# robot.net
KiCad netlist of a schematic drawn in EAGLE
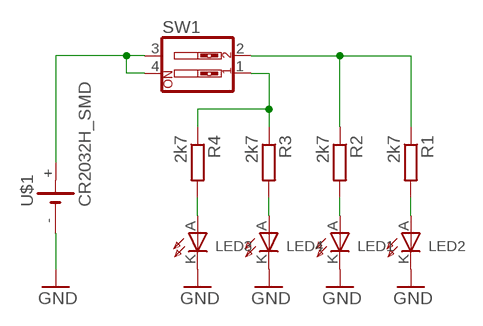
[diagram p0: schematic, sheet 1]

(export (version "E")
  (design (tool "Eeschema 10.0.6"))
  (components
    (comp (ref "LED1")
      (value "LEDREAR")
      (footprint "eagle-import:3MM_REAR")
      (libsource (lib "eagle-import") (part "LEDREAR"))
    )
    (comp (ref "LED2")
      (value "LEDREAR")
      (footprint "eagle-import:3MM_REAR")
      (libsource (lib "eagle-import") (part "LEDREAR"))
    )
    (comp (ref "LED3")
      (value "LED3MMH")
      (footprint "eagle-import:3MM_H")
      (libsource (lib "eagle-import") (part "LED3MMH"))
    )
    (comp (ref "LED4")
      (value "LED3MMH")
      (footprint "eagle-import:3MM_H")
      (libsource (lib "eagle-import") (part "LED3MMH"))
    )
    (comp (ref "R1")
      (value "2k7")
      (footprint "eagle-import:0204_7")
      (libsource (lib "eagle-import") (part "R-EU_0204/7"))
    )
    (comp (ref "R2")
      (value "2k7")
      (footprint "eagle-import:0204_7")
      (libsource (lib "eagle-import") (part "R-EU_0204/7"))
    )
    (comp (ref "R3")
      (value "2k7")
      (footprint "eagle-import:0204_7")
      (libsource (lib "eagle-import") (part "R-EU_0204/7"))
    )
    (comp (ref "R4")
      (value "2k7")
      (footprint "eagle-import:0204_7")
      (libsource (lib "eagle-import") (part "R-EU_0204/7"))
    )
    (comp (ref "SW1")
      (value "SW_DIP-2")
      (footprint "eagle-import:EDG-02")
      (libsource (lib "eagle-import") (part "SW_DIP-2"))
    )
    (comp (ref "U$1")
      (value "CR2032H_SMD")
      (footprint "eagle-import:CR2032H_SMD")
      (libsource (lib "eagle-import") (part "CR2032H_SMD"))
    )
  )
  (nets
    (net (code "1") (name "GND") (class "Default")
      (node (ref "LED1") (pin "K") (pinfunction "K_K") (pintype "passive"))
      (node (ref "LED2") (pin "K") (pinfunction "K_K") (pintype "passive"))
      (node (ref "LED3") (pin "K") (pinfunction "K_K") (pintype "passive"))
      (node (ref "LED4") (pin "K") (pinfunction "K_K") (pintype "passive"))
      (node (ref "U$1") (pin "-") (pinfunction "-_-") (pintype "passive"))
    )
    (net (code "2") (name "Net-(LED1-PadA)") (class "Default")
      (node (ref "LED1") (pin "A") (pinfunction "A_A") (pintype "passive"))
      (node (ref "R2") (pin "2") (pinfunction "2_2") (pintype "passive"))
    )
    (net (code "3") (name "Net-(LED2-PadA)") (class "Default")
      (node (ref "LED2") (pin "A") (pinfunction "A_A") (pintype "passive"))
      (node (ref "R1") (pin "2") (pinfunction "2_2") (pintype "passive"))
    )
    (net (code "4") (name "Net-(LED3-PadA)") (class "Default")
      (node (ref "LED3") (pin "A") (pinfunction "A_A") (pintype "passive"))
      (node (ref "R4") (pin "2") (pinfunction "2_2") (pintype "passive"))
    )
    (net (code "5") (name "Net-(LED4-PadA)") (class "Default")
      (node (ref "LED4") (pin "A") (pinfunction "A_A") (pintype "passive"))
      (node (ref "R3") (pin "2") (pinfunction "2_2") (pintype "passive"))
    )
    (net (code "6") (name "Net-(R1-Pad1)") (class "Default")
      (node (ref "R1") (pin "1") (pinfunction "1_1") (pintype "passive"))
      (node (ref "R2") (pin "1") (pinfunction "1_1") (pintype "passive"))
      (node (ref "SW1") (pin "2") (pinfunction "2_2") (pintype "passive"))
    )
    (net (code "7") (name "Net-(R3-Pad1)") (class "Default")
      (node (ref "R3") (pin "1") (pinfunction "1_1") (pintype "passive"))
      (node (ref "R4") (pin "1") (pinfunction "1_1") (pintype "passive"))
      (node (ref "SW1") (pin "1") (pinfunction "1_1") (pintype "passive"))
    )
    (net (code "8") (name "Net-(SW1-Pad3)") (class "Default")
      (node (ref "SW1") (pin "3") (pinfunction "3_3") (pintype "passive"))
      (node (ref "SW1") (pin "4") (pinfunction "4_4") (pintype "passive"))
      (node (ref "U$1") (pin "+") (pinfunction "+_+") (pintype "passive"))
    )
  )
)
